# SCH_course-project-oscilloscope_2025-03-.net
KiCad netlist of a schematic drawn in EasyEDA
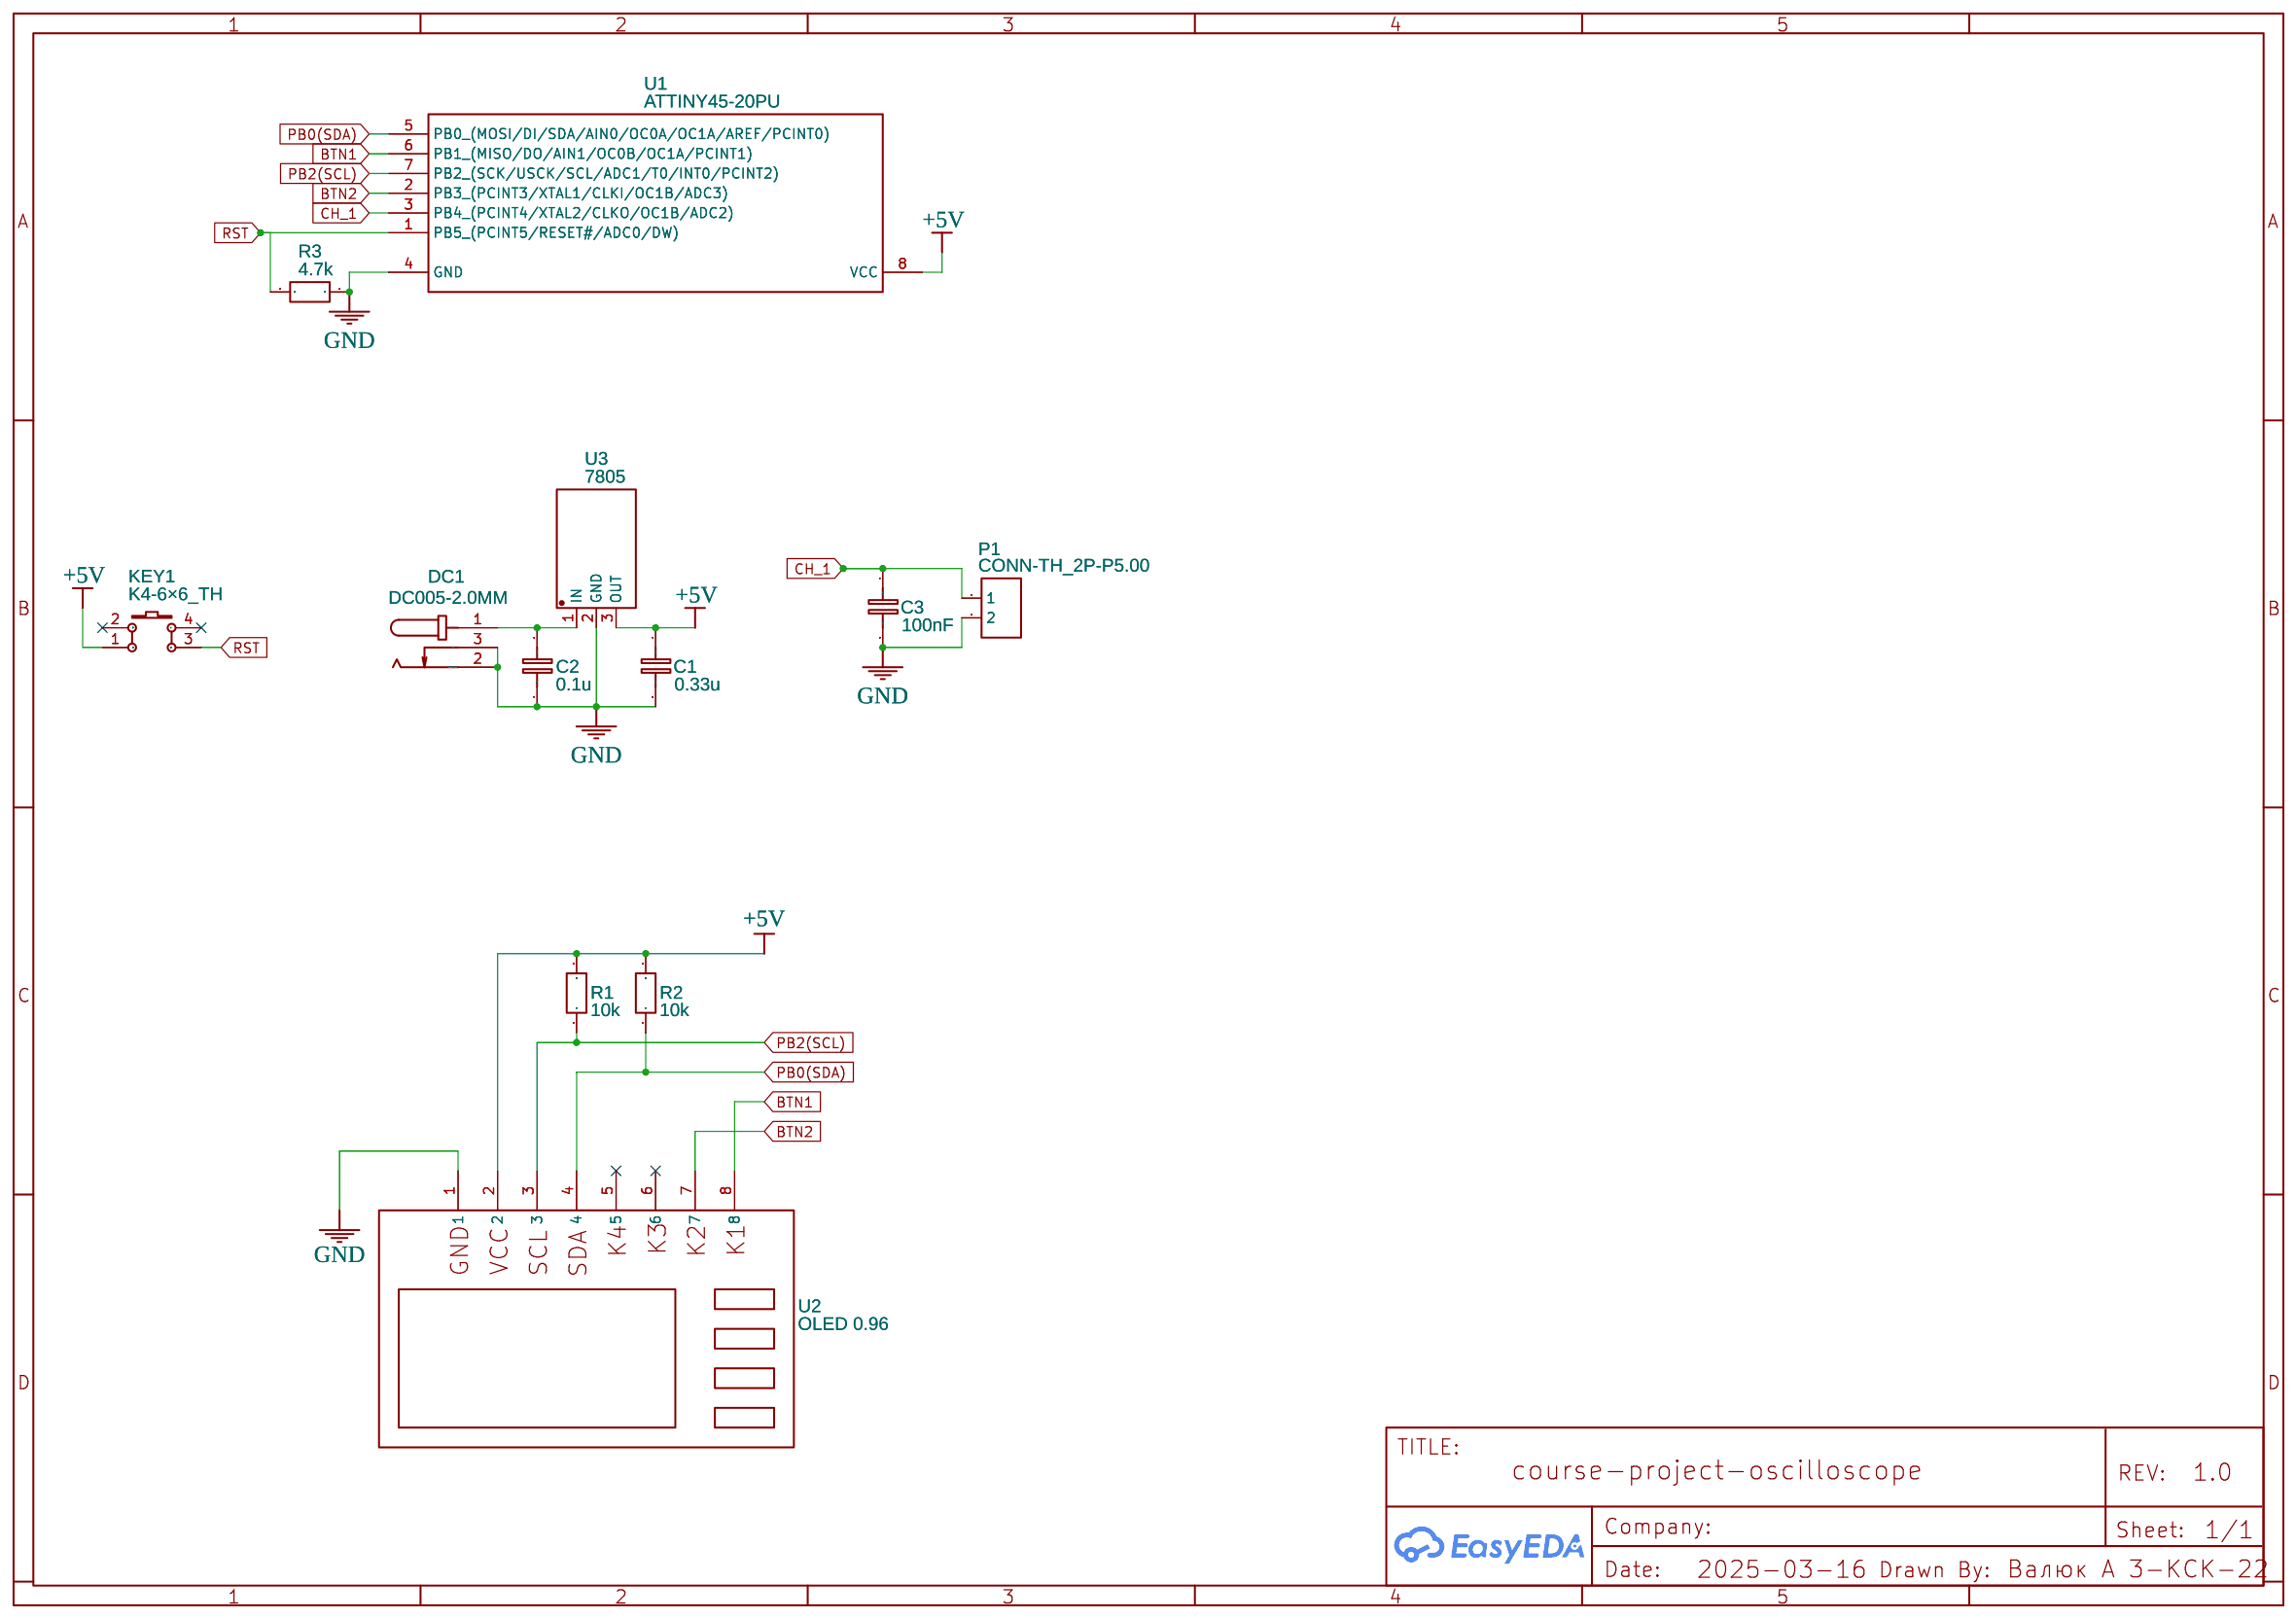
[diagram p0: schematic sheet]

(export (version "E")
  (design (tool "Eeschema 10.0.6"))
  (components
    (comp (ref "C1") (value "0.33u") (libsource (lib "") (part "C_RAD-0.1_EU")))
    (comp (ref "C2") (value "0.1u") (libsource (lib "") (part "C_RAD-0.1_EU")))
    (comp (ref "C3") (value "100nF") (libsource (lib "") (part "C_RAD-0.1_EU")))
    (comp (ref "DC1")
      (value "DC005-2.0MM")
      (fields (field (name "Manufacturer") "SOFNG"))
      (libsource (lib "") (part "DC005-2.0MM"))
    )
    (comp (ref "KEY1")
      (value "K4-6×6_TH")
      (fields (field (name "Manufacturer Part") "K2-1102DP-E4SW-04") (field (name "Manufacturer") "韩国韩荣"))
      (libsource (lib "") (part "K4-6×6_TH"))
    )
    (comp (ref "P1") (value "CONN-TH_2P-P5.00") (libsource (lib "") (part "CONN-TH_2P-P5.00")))
    (comp (ref "R1") (value "10k") (libsource (lib "") (part "R_AXIAL-0.3_EU")))
    (comp (ref "R2") (value "10k") (libsource (lib "") (part "R_AXIAL-0.3_EU")))
    (comp (ref "R3") (value "4.7k") (libsource (lib "") (part "R_AXIAL-0.3_EU_1")))
    (comp (ref "U1")
      (value "ATTINY45-20PU")
      (fields (field (name "Manufacturer") "MICROCHIP(美国微芯)"))
      (libsource (lib "") (part "ATTINY45-20PU"))
    )
    (comp (ref "U2") (value "OLED 0.96") (libsource (lib "") (part "OLED 0.96")))
    (comp (ref "U3")
      (value "7805")
      (fields (field (name "Manufacturer") "BLUE ROCKET(蓝箭)"))
      (libsource (lib "") (part "7805"))
    )
  )
  (nets
    (net (code "1") (name "+5V") (class "Default")
      (node (ref "C1") (pin "1") (pinfunction "1_1") (pintype "unspecified"))
      (node (ref "KEY1") (pin "1") (pinfunction "1_1") (pintype "unspecified"))
      (node (ref "R1") (pin "2") (pinfunction "2_2") (pintype "unspecified"))
      (node (ref "R2") (pin "2") (pinfunction "2_2") (pintype "unspecified"))
      (node (ref "U1") (pin "8") (pinfunction "VCC_8") (pintype "passive"))
      (node (ref "U2") (pin "2") (pinfunction "2_2") (pintype "unspecified"))
      (node (ref "U3") (pin "3") (pinfunction "OUT_3") (pintype "unspecified"))
    )
    (net (code "2") (name "BTN1") (class "Default")
      (node (ref "U1") (pin "6") (pinfunction "PB1_(MISO/DO/AIN1/OC0B/OC1A/PCINT1)_6") (pintype "bidirectional"))
      (node (ref "U2") (pin "8") (pinfunction "8_8") (pintype "unspecified"))
    )
    (net (code "3") (name "BTN2") (class "Default")
      (node (ref "U1") (pin "2") (pinfunction "PB3_(PCINT3/XTAL1/CLKI/OC1B/ADC3)_2") (pintype "bidirectional"))
      (node (ref "U2") (pin "7") (pinfunction "7_7") (pintype "unspecified"))
    )
    (net (code "4") (name "CH_1") (class "Default")
      (node (ref "C3") (pin "1") (pinfunction "1_1") (pintype "unspecified"))
      (node (ref "P1") (pin "1") (pinfunction "1_1") (pintype "unspecified"))
      (node (ref "U1") (pin "3") (pinfunction "PB4_(PCINT4/XTAL2/CLKO/OC1B/ADC2)_3") (pintype "bidirectional"))
    )
    (net (code "5") (name "GND") (class "Default")
      (node (ref "C1") (pin "2") (pinfunction "2_2") (pintype "unspecified"))
      (node (ref "C2") (pin "2") (pinfunction "2_2") (pintype "unspecified"))
      (node (ref "C3") (pin "2") (pinfunction "2_2") (pintype "unspecified"))
      (node (ref "DC1") (pin "2") (pinfunction "2_2") (pintype "unspecified"))
      (node (ref "DC1") (pin "3") (pinfunction "3_3") (pintype "unspecified"))
      (node (ref "P1") (pin "2") (pinfunction "2_2") (pintype "unspecified"))
      (node (ref "R3") (pin "1") (pinfunction "1_1") (pintype "unspecified"))
      (node (ref "U1") (pin "4") (pinfunction "GND_4") (pintype "passive"))
      (node (ref "U2") (pin "1") (pinfunction "1_1") (pintype "unspecified"))
      (node (ref "U3") (pin "2") (pinfunction "GND_2") (pintype "unspecified"))
    )
    (net (code "6") (name "Net-(U3-IN)") (class "Default")
      (node (ref "C2") (pin "1") (pinfunction "1_1") (pintype "unspecified"))
      (node (ref "DC1") (pin "1") (pinfunction "1_1") (pintype "unspecified"))
      (node (ref "U3") (pin "1") (pinfunction "IN_1") (pintype "unspecified"))
    )
    (net (code "7") (name "PB0(SDA)") (class "Default")
      (node (ref "R2") (pin "1") (pinfunction "1_1") (pintype "unspecified"))
      (node (ref "U1") (pin "5") (pinfunction "PB0_(MOSI/DI/SDA/AIN0/OC0A/OC1A/AREF/PCINT0)_5") (pintype "bidirectional"))
      (node (ref "U2") (pin "4") (pinfunction "4_4") (pintype "unspecified"))
    )
    (net (code "8") (name "PB2(SCL)") (class "Default")
      (node (ref "R1") (pin "1") (pinfunction "1_1") (pintype "unspecified"))
      (node (ref "U1") (pin "7") (pinfunction "PB2_(SCK/USCK/SCL/ADC1/T0/INT0/PCINT2)_7") (pintype "bidirectional"))
      (node (ref "U2") (pin "3") (pinfunction "3_3") (pintype "unspecified"))
    )
    (net (code "9") (name "RST") (class "Default")
      (node (ref "KEY1") (pin "3") (pinfunction "3_3") (pintype "unspecified"))
      (node (ref "R3") (pin "2") (pinfunction "2_2") (pintype "unspecified"))
      (node (ref "U1") (pin "1") (pinfunction "PB5_(PCINT5/RESET#/ADC0/DW)_1") (pintype "bidirectional"))
    )
    (net (code "10") (name "unconnected-(KEY1-Pad2)") (class "Default")
      (node (ref "KEY1") (pin "2") (pinfunction "2_2") (pintype "unspecified+no_connect"))
    )
    (net (code "11") (name "unconnected-(KEY1-Pad4)") (class "Default")
      (node (ref "KEY1") (pin "4") (pinfunction "4_4") (pintype "unspecified+no_connect"))
    )
    (net (code "12") (name "unconnected-(U2-Pad5)") (class "Default")
      (node (ref "U2") (pin "5") (pinfunction "5_5") (pintype "unspecified+no_connect"))
    )
    (net (code "13") (name "unconnected-(U2-Pad6)") (class "Default")
      (node (ref "U2") (pin "6") (pinfunction "6_6") (pintype "unspecified+no_connect"))
    )
  )
)
